# teensy_base.net
KiCad netlist of a schematic drawn in Altium Designer
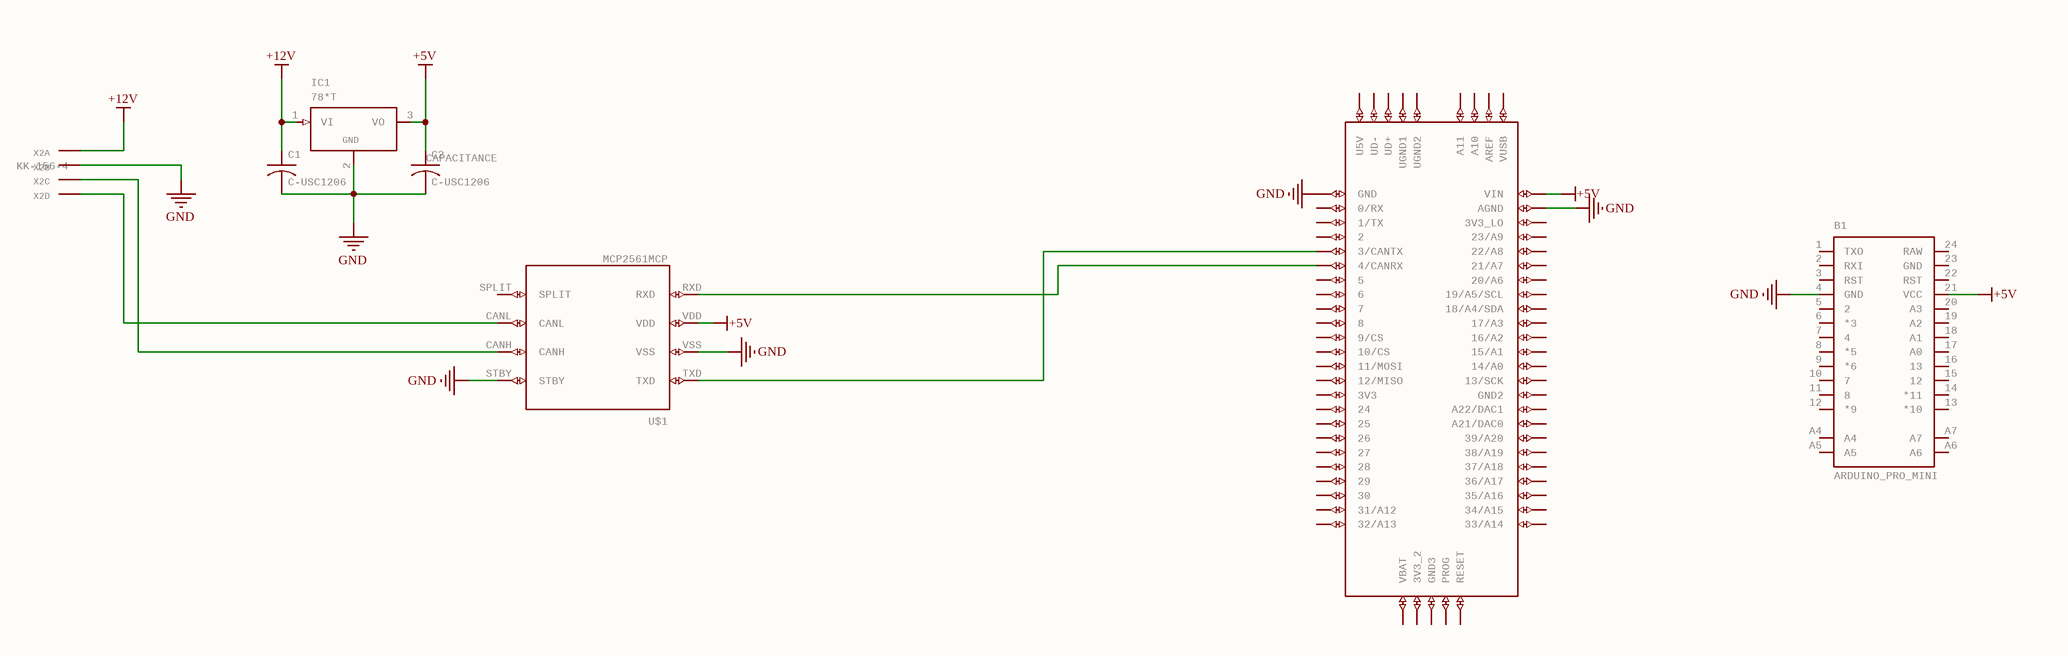
[diagram p0: teensy_base.SchDoc]

(export (version "E")
  (design (tool "Eeschema 10.0.6"))
  (components
    (comp (ref "B1")
      (value "ARDUINO_PRO_MINI")
      (footprint "ARDUINO_PRO_MINI")
      (libsource (lib "SparkFun-Boards") (part "ARDUINO_PRO_MINI"))
    )
    (comp (ref "C1")
      (value "C-USC1206")
      (footprint "C1206")
      (description "CAPACITOR, American symbol")
      (libsource (lib "rcl") (part "C-USC1206"))
    )
    (comp (ref "C2")
      (value "C-USC1206")
      (footprint "C1206")
      (description "CAPACITOR, American symbol")
      (fields (field (name "CAPACITANCE") "CAPACITANCE"))
      (libsource (lib "rcl") (part "C-USC1206"))
    )
    (comp (ref "IC1")
      (value "78*T")
      (footprint "TO220H")
      (fields (field (name "GND") "GND"))
      (libsource (lib "linear") (part "78*T"))
    )
    (comp (ref "U$1")
      (value "MCP2561MCP")
      (footprint "MCP2561_PDIP")
      (fields (field (name "LIBRARYNAME") "PoJD"))
      (libsource (lib "PoJD") (part "MCP2561MCP"))
    )
    (comp (ref "U$2")
      (value "TEENSY_3.5/3.6")
      (footprint "TEENSY_3.5/3.6")
      (libsource (lib "Teensy356") (part "TEENSY_3.5/3.6"))
    )
    (comp (ref "X2")
      (value "KK-156-4")
      (footprint "KK-156-4")
      (description "KK 156 HEADER   Source: http://www.molex.com/pdm_docs/sd/026604100_sd.pdf")
      (fields (field (name "MF") "MF") (field (name "MPN") "MPN"))
      (libsource (lib "con-molex") (part "KK-156-4"))
    )
  )
  (nets
    (net (code "1") (name "+5V") (class "Default")
      (node (ref "B1") (pin "21") (pinfunction "VCC_21") (pintype "power_in"))
      (node (ref "C2") (pin "1") (pinfunction "1_1") (pintype "passive"))
      (node (ref "IC1") (pin "3") (pinfunction "VO_3") (pintype "passive"))
      (node (ref "U$1") (pin "VDD") (pinfunction "VDD_VDD") (pintype "bidirectional"))
      (node (ref "U$2") (pin "VIN") (pinfunction "VIN_VIN") (pintype "bidirectional"))
    )
    (net (code "2") (name "+12V") (class "Default")
      (node (ref "C1") (pin "1") (pinfunction "1_1") (pintype "passive"))
      (node (ref "IC1") (pin "1") (pinfunction "VI_1") (pintype "input"))
      (node (ref "X2") (pin "1") (pinfunction "S_1") (pintype "passive"))
    )
    (net (code "3") (name "GND") (class "Default")
      (node (ref "B1") (pin "4") (pinfunction "GND_4") (pintype "power_in"))
      (node (ref "C1") (pin "2") (pinfunction "2_2") (pintype "passive"))
      (node (ref "C2") (pin "2") (pinfunction "2_2") (pintype "passive"))
      (node (ref "IC1") (pin "2") (pinfunction "GND_2") (pintype "passive"))
      (node (ref "U$1") (pin "STBY") (pinfunction "STBY_STBY") (pintype "bidirectional"))
      (node (ref "U$1") (pin "VSS") (pinfunction "VSS_VSS") (pintype "bidirectional"))
      (node (ref "U$2") (pin "AGND") (pinfunction "AGND_AGND") (pintype "bidirectional"))
      (node (ref "U$2") (pin "GND") (pinfunction "GND_GND") (pintype "bidirectional"))
      (node (ref "X2") (pin "2") (pinfunction "S_2") (pintype "passive"))
    )
    (net (code "4") (name "Net-(U$1-PadRXD)") (class "Default")
      (node (ref "U$1") (pin "RXD") (pinfunction "RXD_RXD") (pintype "bidirectional"))
      (node (ref "U$2") (pin "4/CANRX") (pinfunction "4/CANRX_4/CANRX") (pintype "bidirectional"))
    )
    (net (code "5") (name "Net-(U$1-PadTXD)") (class "Default")
      (node (ref "U$1") (pin "TXD") (pinfunction "TXD_TXD") (pintype "bidirectional"))
      (node (ref "U$2") (pin "3/CANTX") (pinfunction "3/CANTX_3/CANTX") (pintype "bidirectional"))
    )
    (net (code "6") (name "Net-(X2C-S)") (class "Default")
      (node (ref "U$1") (pin "CANH") (pinfunction "CANH_CANH") (pintype "bidirectional"))
      (node (ref "X2") (pin "3") (pinfunction "S_3") (pintype "passive"))
    )
    (net (code "7") (name "Net-(X2D-S)") (class "Default")
      (node (ref "U$1") (pin "CANL") (pinfunction "CANL_CANL") (pintype "bidirectional"))
      (node (ref "X2") (pin "4") (pinfunction "S_4") (pintype "passive"))
    )
    (net (code "8") (name "unconnected-(B1-*3-Pad6)") (class "Default")
      (node (ref "B1") (pin "6") (pinfunction "*3_6") (pintype "bidirectional"))
    )
    (net (code "9") (name "unconnected-(B1-*5-Pad8)") (class "Default")
      (node (ref "B1") (pin "8") (pinfunction "*5_8") (pintype "bidirectional"))
    )
    (net (code "10") (name "unconnected-(B1-*6-Pad9)") (class "Default")
      (node (ref "B1") (pin "9") (pinfunction "*6_9") (pintype "bidirectional"))
    )
    (net (code "11") (name "unconnected-(B1-*9-Pad12)") (class "Default")
      (node (ref "B1") (pin "12") (pinfunction "*9_12") (pintype "bidirectional"))
    )
    (net (code "12") (name "unconnected-(B1-*10-Pad13)") (class "Default")
      (node (ref "B1") (pin "13") (pinfunction "*10_13") (pintype "bidirectional"))
    )
    (net (code "13") (name "unconnected-(B1-*11-Pad14)") (class "Default")
      (node (ref "B1") (pin "14") (pinfunction "*11_14") (pintype "bidirectional"))
    )
    (net (code "14") (name "unconnected-(B1-2-Pad5)") (class "Default")
      (node (ref "B1") (pin "5") (pinfunction "2_5") (pintype "bidirectional"))
    )
    (net (code "15") (name "unconnected-(B1-4-Pad7)") (class "Default")
      (node (ref "B1") (pin "7") (pinfunction "4_7") (pintype "bidirectional"))
    )
    (net (code "16") (name "unconnected-(B1-7-Pad10)") (class "Default")
      (node (ref "B1") (pin "10") (pinfunction "7_10") (pintype "bidirectional"))
    )
    (net (code "17") (name "unconnected-(B1-8-Pad11)") (class "Default")
      (node (ref "B1") (pin "11") (pinfunction "8_11") (pintype "bidirectional"))
    )
    (net (code "18") (name "unconnected-(B1-12-Pad15)") (class "Default")
      (node (ref "B1") (pin "15") (pinfunction "12_15") (pintype "bidirectional"))
    )
    (net (code "19") (name "unconnected-(B1-13-Pad16)") (class "Default")
      (node (ref "B1") (pin "16") (pinfunction "13_16") (pintype "bidirectional"))
    )
    (net (code "20") (name "unconnected-(B1-A0-Pad17)") (class "Default")
      (node (ref "B1") (pin "17") (pinfunction "A0_17") (pintype "bidirectional"))
    )
    (net (code "21") (name "unconnected-(B1-A1-Pad18)") (class "Default")
      (node (ref "B1") (pin "18") (pinfunction "A1_18") (pintype "bidirectional"))
    )
    (net (code "22") (name "unconnected-(B1-A2-Pad19)") (class "Default")
      (node (ref "B1") (pin "19") (pinfunction "A2_19") (pintype "bidirectional"))
    )
    (net (code "23") (name "unconnected-(B1-A3-Pad20)") (class "Default")
      (node (ref "B1") (pin "20") (pinfunction "A3_20") (pintype "bidirectional"))
    )
    (net (code "24") (name "unconnected-(B1-GND-Pad23)") (class "Default")
      (node (ref "B1") (pin "23") (pinfunction "GND_23") (pintype "power_in"))
    )
    (net (code "25") (name "unconnected-(B1-PadA4)") (class "Default")
      (node (ref "B1") (pin "A4") (pinfunction "A4_A4") (pintype "bidirectional"))
    )
    (net (code "26") (name "unconnected-(B1-PadA5)") (class "Default")
      (node (ref "B1") (pin "A5") (pinfunction "A5_A5") (pintype "bidirectional"))
    )
    (net (code "27") (name "unconnected-(B1-PadA6)") (class "Default")
      (node (ref "B1") (pin "A6") (pinfunction "A6_A6") (pintype "bidirectional"))
    )
    (net (code "28") (name "unconnected-(B1-PadA7)") (class "Default")
      (node (ref "B1") (pin "A7") (pinfunction "A7_A7") (pintype "bidirectional"))
    )
    (net (code "29") (name "unconnected-(B1-RAW-Pad24)") (class "Default")
      (node (ref "B1") (pin "24") (pinfunction "RAW_24") (pintype "power_in"))
    )
    (net (code "30") (name "unconnected-(B1-RST-Pad3)") (class "Default")
      (node (ref "B1") (pin "3") (pinfunction "RST_3") (pintype "bidirectional"))
    )
    (net (code "31") (name "unconnected-(B1-RST-Pad22)") (class "Default")
      (node (ref "B1") (pin "22") (pinfunction "RST_22") (pintype "bidirectional"))
    )
    (net (code "32") (name "unconnected-(B1-RXI-Pad2)") (class "Default")
      (node (ref "B1") (pin "2") (pinfunction "RXI_2") (pintype "bidirectional"))
    )
    (net (code "33") (name "unconnected-(B1-TXO-Pad1)") (class "Default")
      (node (ref "B1") (pin "1") (pinfunction "TXO_1") (pintype "bidirectional"))
    )
    (net (code "34") (name "unconnected-(U$1-PadSPLIT)") (class "Default")
      (node (ref "U$1") (pin "SPLIT") (pinfunction "SPLIT_SPLIT") (pintype "bidirectional"))
    )
    (net (code "35") (name "unconnected-(U$2-A21{slash}DAC0-Pad21{slash}DAC0)") (class "Default")
      (node (ref "U$2") (pin "21/DAC0") (pinfunction "A21/DAC0_21/DAC0") (pintype "bidirectional"))
    )
    (net (code "36") (name "unconnected-(U$2-Pad0{slash}RX)") (class "Default")
      (node (ref "U$2") (pin "0/RX") (pinfunction "0/RX_0/RX") (pintype "bidirectional"))
    )
    (net (code "37") (name "unconnected-(U$2-Pad1{slash}TX)") (class "Default")
      (node (ref "U$2") (pin "1/TX") (pinfunction "1/TX_1/TX") (pintype "bidirectional"))
    )
    (net (code "38") (name "unconnected-(U$2-Pad2)") (class "Default")
      (node (ref "U$2") (pin "2") (pinfunction "2_2") (pintype "bidirectional"))
    )
    (net (code "39") (name "unconnected-(U$2-Pad3V3)") (class "Default")
      (node (ref "U$2") (pin "3V3") (pinfunction "3V3_3V3") (pintype "bidirectional"))
    )
    (net (code "40") (name "unconnected-(U$2-Pad3V3_2)") (class "Default")
      (node (ref "U$2") (pin "3V3_2") (pinfunction "3V3_2_3V3_2") (pintype "bidirectional"))
    )
    (net (code "41") (name "unconnected-(U$2-Pad3V3_LO)") (class "Default")
      (node (ref "U$2") (pin "3V3_LO") (pinfunction "3V3_LO_3V3_LO") (pintype "bidirectional"))
    )
    (net (code "42") (name "unconnected-(U$2-Pad5)") (class "Default")
      (node (ref "U$2") (pin "5") (pinfunction "5_5") (pintype "bidirectional"))
    )
    (net (code "43") (name "unconnected-(U$2-Pad6)") (class "Default")
      (node (ref "U$2") (pin "6") (pinfunction "6_6") (pintype "bidirectional"))
    )
    (net (code "44") (name "unconnected-(U$2-Pad7)") (class "Default")
      (node (ref "U$2") (pin "7") (pinfunction "7_7") (pintype "bidirectional"))
    )
    (net (code "45") (name "unconnected-(U$2-Pad8)") (class "Default")
      (node (ref "U$2") (pin "8") (pinfunction "8_8") (pintype "bidirectional"))
    )
    (net (code "46") (name "unconnected-(U$2-Pad9{slash}CS)") (class "Default")
      (node (ref "U$2") (pin "9/CS") (pinfunction "9/CS_9/CS") (pintype "bidirectional"))
    )
    (net (code "47") (name "unconnected-(U$2-Pad10{slash}CS)") (class "Default")
      (node (ref "U$2") (pin "10/CS") (pinfunction "10/CS_10/CS") (pintype "bidirectional"))
    )
    (net (code "48") (name "unconnected-(U$2-Pad11{slash}MOSI)") (class "Default")
      (node (ref "U$2") (pin "11/MOSI") (pinfunction "11/MOSI_11/MOSI") (pintype "bidirectional"))
    )
    (net (code "49") (name "unconnected-(U$2-Pad12{slash}MISO)") (class "Default")
      (node (ref "U$2") (pin "12/MISO") (pinfunction "12/MISO_12/MISO") (pintype "bidirectional"))
    )
    (net (code "50") (name "unconnected-(U$2-Pad13{slash}SCK)") (class "Default")
      (node (ref "U$2") (pin "13/SCK") (pinfunction "13/SCK_13/SCK") (pintype "bidirectional"))
    )
    (net (code "51") (name "unconnected-(U$2-Pad14{slash}A0)") (class "Default")
      (node (ref "U$2") (pin "14/A0") (pinfunction "14/A0_14/A0") (pintype "bidirectional"))
    )
    (net (code "52") (name "unconnected-(U$2-Pad15{slash}A1)") (class "Default")
      (node (ref "U$2") (pin "15/A1") (pinfunction "15/A1_15/A1") (pintype "bidirectional"))
    )
    (net (code "53") (name "unconnected-(U$2-Pad16{slash}A2)") (class "Default")
      (node (ref "U$2") (pin "16/A2") (pinfunction "16/A2_16/A2") (pintype "bidirectional"))
    )
    (net (code "54") (name "unconnected-(U$2-Pad17{slash}A3)") (class "Default")
      (node (ref "U$2") (pin "17/A3") (pinfunction "17/A3_17/A3") (pintype "bidirectional"))
    )
    (net (code "55") (name "unconnected-(U$2-Pad18{slash}A4{slash}SDA)") (class "Default")
      (node (ref "U$2") (pin "18/A4/SDA") (pinfunction "18/A4/SDA_18/A4/SDA") (pintype "bidirectional"))
    )
    (net (code "56") (name "unconnected-(U$2-Pad19{slash}A5{slash}SCL)") (class "Default")
      (node (ref "U$2") (pin "19/A5/SCL") (pinfunction "19/A5/SCL_19/A5/SCL") (pintype "bidirectional"))
    )
    (net (code "57") (name "unconnected-(U$2-Pad20{slash}A6)") (class "Default")
      (node (ref "U$2") (pin "20/A6") (pinfunction "20/A6_20/A6") (pintype "bidirectional"))
    )
    (net (code "58") (name "unconnected-(U$2-Pad21{slash}A7)") (class "Default")
      (node (ref "U$2") (pin "21/A7") (pinfunction "21/A7_21/A7") (pintype "bidirectional"))
    )
    (net (code "59") (name "unconnected-(U$2-Pad22{slash}A8)") (class "Default")
      (node (ref "U$2") (pin "22/A8") (pinfunction "22/A8_22/A8") (pintype "bidirectional"))
    )
    (net (code "60") (name "unconnected-(U$2-Pad23{slash}A9)") (class "Default")
      (node (ref "U$2") (pin "23/A9") (pinfunction "23/A9_23/A9") (pintype "bidirectional"))
    )
    (net (code "61") (name "unconnected-(U$2-Pad24)") (class "Default")
      (node (ref "U$2") (pin "24") (pinfunction "24_24") (pintype "bidirectional"))
    )
    (net (code "62") (name "unconnected-(U$2-Pad25)") (class "Default")
      (node (ref "U$2") (pin "25") (pinfunction "25_25") (pintype "bidirectional"))
    )
    (net (code "63") (name "unconnected-(U$2-Pad26)") (class "Default")
      (node (ref "U$2") (pin "26") (pinfunction "26_26") (pintype "bidirectional"))
    )
    (net (code "64") (name "unconnected-(U$2-Pad27)") (class "Default")
      (node (ref "U$2") (pin "27") (pinfunction "27_27") (pintype "bidirectional"))
    )
    (net (code "65") (name "unconnected-(U$2-Pad28)") (class "Default")
      (node (ref "U$2") (pin "28") (pinfunction "28_28") (pintype "bidirectional"))
    )
    (net (code "66") (name "unconnected-(U$2-Pad29)") (class "Default")
      (node (ref "U$2") (pin "29") (pinfunction "29_29") (pintype "bidirectional"))
    )
    (net (code "67") (name "unconnected-(U$2-Pad30)") (class "Default")
      (node (ref "U$2") (pin "30") (pinfunction "30_30") (pintype "bidirectional"))
    )
    (net (code "68") (name "unconnected-(U$2-Pad31{slash}A12)") (class "Default")
      (node (ref "U$2") (pin "31/A12") (pinfunction "31/A12_31/A12") (pintype "bidirectional"))
    )
    (net (code "69") (name "unconnected-(U$2-Pad32{slash}A13)") (class "Default")
      (node (ref "U$2") (pin "32/A13") (pinfunction "32/A13_32/A13") (pintype "bidirectional"))
    )
    (net (code "70") (name "unconnected-(U$2-Pad33{slash}A14)") (class "Default")
      (node (ref "U$2") (pin "33/A14") (pinfunction "33/A14_33/A14") (pintype "bidirectional"))
    )
    (net (code "71") (name "unconnected-(U$2-Pad34{slash}A15)") (class "Default")
      (node (ref "U$2") (pin "34/A15") (pinfunction "34/A15_34/A15") (pintype "bidirectional"))
    )
    (net (code "72") (name "unconnected-(U$2-Pad35{slash}A16)") (class "Default")
      (node (ref "U$2") (pin "35/A16") (pinfunction "35/A16_35/A16") (pintype "bidirectional"))
    )
    (net (code "73") (name "unconnected-(U$2-Pad36{slash}A17)") (class "Default")
      (node (ref "U$2") (pin "36/A17") (pinfunction "36/A17_36/A17") (pintype "bidirectional"))
    )
    (net (code "74") (name "unconnected-(U$2-Pad37{slash}A18)") (class "Default")
      (node (ref "U$2") (pin "37/A18") (pinfunction "37/A18_37/A18") (pintype "bidirectional"))
    )
    (net (code "75") (name "unconnected-(U$2-Pad38{slash}A19)") (class "Default")
      (node (ref "U$2") (pin "38/A19") (pinfunction "38/A19_38/A19") (pintype "bidirectional"))
    )
    (net (code "76") (name "unconnected-(U$2-Pad39{slash}A20)") (class "Default")
      (node (ref "U$2") (pin "39/A20") (pinfunction "39/A20_39/A20") (pintype "bidirectional"))
    )
    (net (code "77") (name "unconnected-(U$2-PadA10)") (class "Default")
      (node (ref "U$2") (pin "A10") (pinfunction "A10_A10") (pintype "bidirectional"))
    )
    (net (code "78") (name "unconnected-(U$2-PadA11)") (class "Default")
      (node (ref "U$2") (pin "A11") (pinfunction "A11_A11") (pintype "bidirectional"))
    )
    (net (code "79") (name "unconnected-(U$2-PadA22{slash}DAC1)") (class "Default")
      (node (ref "U$2") (pin "A22/DAC1") (pinfunction "A22/DAC1_A22/DAC1") (pintype "bidirectional"))
    )
    (net (code "80") (name "unconnected-(U$2-PadAREF)") (class "Default")
      (node (ref "U$2") (pin "AREF") (pinfunction "AREF_AREF") (pintype "bidirectional"))
    )
    (net (code "81") (name "unconnected-(U$2-PadGND2)") (class "Default")
      (node (ref "U$2") (pin "GND2") (pinfunction "GND2_GND2") (pintype "bidirectional"))
    )
    (net (code "82") (name "unconnected-(U$2-PadGND3)") (class "Default")
      (node (ref "U$2") (pin "GND3") (pinfunction "GND3_GND3") (pintype "bidirectional"))
    )
    (net (code "83") (name "unconnected-(U$2-PadPROG)") (class "Default")
      (node (ref "U$2") (pin "PROG") (pinfunction "PROG_PROG") (pintype "bidirectional"))
    )
    (net (code "84") (name "unconnected-(U$2-PadRESET)") (class "Default")
      (node (ref "U$2") (pin "RESET") (pinfunction "RESET_RESET") (pintype "bidirectional"))
    )
    (net (code "85") (name "unconnected-(U$2-PadU5V)") (class "Default")
      (node (ref "U$2") (pin "U5V") (pinfunction "U5V_U5V") (pintype "bidirectional"))
    )
    (net (code "86") (name "unconnected-(U$2-PadUD+)") (class "Default")
      (node (ref "U$2") (pin "UD+") (pinfunction "UD+_UD+") (pintype "bidirectional"))
    )
    (net (code "87") (name "unconnected-(U$2-PadUD-)") (class "Default")
      (node (ref "U$2") (pin "UD-") (pinfunction "UD-_UD-") (pintype "bidirectional"))
    )
    (net (code "88") (name "unconnected-(U$2-PadUGND1)") (class "Default")
      (node (ref "U$2") (pin "UGND1") (pinfunction "UGND1_UGND1") (pintype "bidirectional"))
    )
    (net (code "89") (name "unconnected-(U$2-PadUGND2)") (class "Default")
      (node (ref "U$2") (pin "UGND2") (pinfunction "UGND2_UGND2") (pintype "bidirectional"))
    )
    (net (code "90") (name "unconnected-(U$2-PadVBAT)") (class "Default")
      (node (ref "U$2") (pin "VBAT") (pinfunction "VBAT_VBAT") (pintype "bidirectional"))
    )
    (net (code "91") (name "unconnected-(U$2-PadVUSB)") (class "Default")
      (node (ref "U$2") (pin "VUSB") (pinfunction "VUSB_VUSB") (pintype "bidirectional"))
    )
  )
)
